# IMU_breakout.net
KiCad netlist of a schematic drawn in Altium Designer
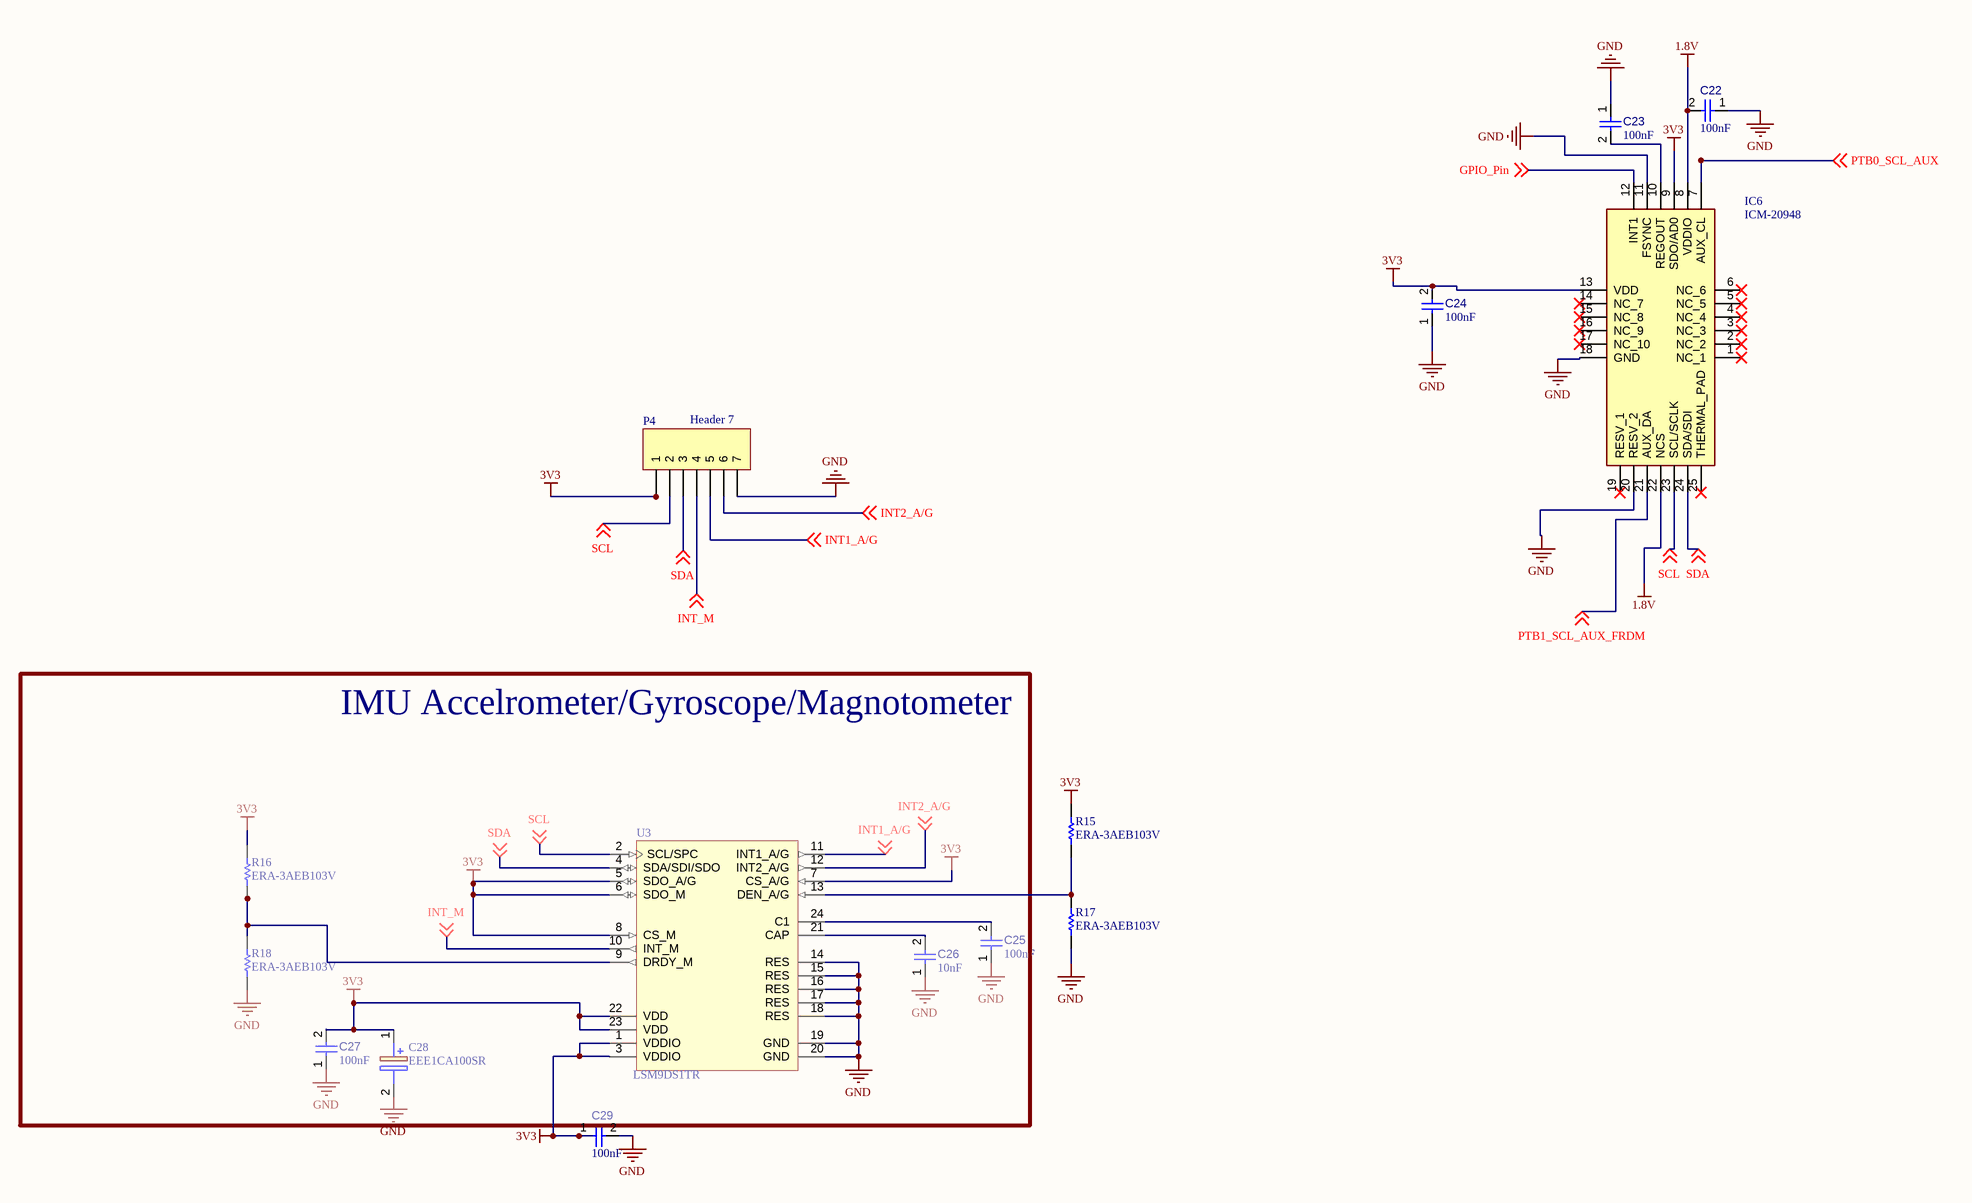
[diagram p0: IMU_breakout.SchDoc]

(export (version "E")
  (design (tool "Eeschema 10.0.6"))
  (components
    (comp (ref "C22")
      (value "100nF")
      (footprint "CAPC1608X90X40ML10T20")
      (description "Chip Capacitor, 100 nF, +/- 10%, 50 V, 0603 (1608 Metric)")
      (fields (field (name "TOLERANCE") "10%") (field (name "Comment") "Capacitor 100 nF +/-10% 50 V 0603"))
      (libsource (lib "James Cook University") (part "CAP-NP-2"))
    )
    (comp (ref "C23")
      (value "100nF")
      (footprint "CAPC1608X90X40ML10T20")
      (description "Chip Capacitor, 100 nF, +/- 10%, 50 V, 0603 (1608 Metric)")
      (fields (field (name "TOLERANCE") "10%") (field (name "Comment") "Capacitor 100 nF +/-10% 50 V 0603"))
      (libsource (lib "James Cook University") (part "CAP-NP-2"))
    )
    (comp (ref "C24")
      (value "100nF")
      (footprint "CAPC1608X90X40ML10T20")
      (description "Chip Capacitor, 100 nF, +/- 10%, 50 V, 0603 (1608 Metric)")
      (fields (field (name "TOLERANCE") "10%") (field (name "Comment") "Capacitor 100 nF +/-10% 50 V 0603"))
      (libsource (lib "James Cook University") (part "CAP-NP-2"))
    )
    (comp (ref "C25")
      (value "100nF")
      (footprint "CAPC1608X90X40ML10T20")
      (description "Chip Capacitor, 100 nF, +/- 10%, 50 V, 0603 (1608 Metric)")
      (fields (field (name "TOLERANCE") "10%") (field (name "Comment") "Capacitor 100 nF +/-10% 50 V 0603"))
      (libsource (lib "James Cook University") (part "CAP-NP-2"))
    )
    (comp (ref "C26")
      (value "10nF")
      (footprint "CAPC0402(1005)60_L")
      (description "Chip Capacitor, 10nF +/-20%, 50V, 0402, Thickness 0.6 mm")
      (fields (field (name "TOLERANCE") "5%") (field (name "Comment") "Capacitor 10nF +/-20% 50V 0402"))
      (libsource (lib "James Cook University") (part "CAP-NP-2"))
    )
    (comp (ref "C27")
      (value "100nF")
      (footprint "CAPC1608X90X40ML10T20")
      (description "Chip Capacitor, 100 nF, +/- 10%, 50 V, 0603 (1608 Metric)")
      (fields (field (name "TOLERANCE") "10%") (field (name "Comment") "Capacitor 100 nF +/-10% 50 V 0603"))
      (libsource (lib "James Cook University") (part "CAP-NP-2"))
    )
    (comp (ref "C28")
      (value "EEE1CA100SR")
      (footprint "SamacSys:CAPAE430X550N")
      (description "Capacitor Polarised")
      (libsource (lib "*") (part "EEE1CA100SR"))
    )
    (comp (ref "C29")
      (value "100nF")
      (footprint "CAPC1608X90X40ML10T20")
      (description "Chip Capacitor, 100 nF, +/- 10%, 50 V, 0603 (1608 Metric)")
      (fields (field (name "TOLERANCE") "10%") (field (name "Comment") "Capacitor 100 nF +/-10% 50 V 0603"))
      (libsource (lib "James Cook University") (part "CAP-NP-2"))
    )
    (comp (ref "IC6")
      (value "ICM-20948")
      (footprint "SamacSys:QFN40P300X300X105-25N-D")
      (description "Integrated Circuit")
      (fields (field (name "MOUSER PART NUMBER") "410-ICM-20948"))
      (libsource (lib "*") (part "ICM-20948"))
    )
    (comp (ref "P4")
      (value "Header 7")
      (footprint "HDR1X7")
      (description "Header, 7-Pin")
      (fields (field (name "PUBLISHER") "Altium Limited"))
      (libsource (lib "Miscellaneous Connectors") (part "Header 7"))
    )
    (comp (ref "R15")
      (value "ERA-3AEB103V")
      (footprint "RESC1608X55X30ML20T20")
      (fields (field (name "MANUFACTURER") "Panasonic"))
      (libsource (lib "Altium Content Vault") (part "RES"))
    )
    (comp (ref "R16")
      (value "ERA-3AEB103V")
      (footprint "RESC1608X55X30ML20T20")
      (fields (field (name "MANUFACTURER") "Panasonic"))
      (libsource (lib "Altium Content Vault") (part "RES"))
    )
    (comp (ref "R17")
      (value "ERA-3AEB103V")
      (footprint "RESC1608X55X30ML20T20")
      (fields (field (name "MANUFACTURER") "Panasonic"))
      (libsource (lib "Altium Content Vault") (part "RES"))
    )
    (comp (ref "R18")
      (value "ERA-3AEB103V")
      (footprint "RESC1608X55X30ML20T20")
      (fields (field (name "MANUFACTURER") "Panasonic"))
      (libsource (lib "Altium Content Vault") (part "RES"))
    )
    (comp (ref "U3")
      (value "LSM9DS1TR")
      (footprint "STM-LGA-24_3500X3000X1000")
      (fields (field (name "PARTNUMBER") "LSM9DS1") (field (name "MANUFACTURER") "STMicroelectronics"))
      (libsource (lib "Altium Content Vault") (part "STM-LSM9DS1-24"))
    )
  )
  (nets
    (net (code "1") (name "1.8V") (class "Default")
      (node (ref "C22") (pin "2") (pinfunction "2_2") (pintype "passive"))
      (node (ref "IC6") (pin "22") (pinfunction "NCS_22") (pintype "passive"))
      (node (ref "IC6") (pin "8") (pinfunction "VDDIO_8") (pintype "passive"))
    )
    (net (code "2") (name "3V3") (class "Default")
      (node (ref "C24") (pin "2") (pinfunction "2_2") (pintype "passive"))
      (node (ref "C27") (pin "2") (pinfunction "2_2") (pintype "passive"))
      (node (ref "C28") (pin "1") (pinfunction "+_1") (pintype "passive"))
      (node (ref "C29") (pin "1") (pinfunction "1_1") (pintype "passive"))
      (node (ref "IC6") (pin "13") (pinfunction "VDD_13") (pintype "passive"))
      (node (ref "IC6") (pin "9") (pinfunction "SDO/AD0_9") (pintype "passive"))
      (node (ref "P4") (pin "1") (pinfunction "1_1") (pintype "passive"))
      (node (ref "R15") (pin "2") (pinfunction "2_2") (pintype "passive"))
      (node (ref "R16") (pin "1") (pinfunction "1_1") (pintype "passive"))
      (node (ref "U3") (pin "1") (pinfunction "VDDIO_1") (pintype "power_in"))
      (node (ref "U3") (pin "22") (pinfunction "VDD_22") (pintype "power_in"))
      (node (ref "U3") (pin "23") (pinfunction "VDD_23") (pintype "power_in"))
      (node (ref "U3") (pin "3") (pinfunction "VDDIO_3") (pintype "power_in"))
      (node (ref "U3") (pin "5") (pinfunction "SDO_A/G_5") (pintype "bidirectional"))
      (node (ref "U3") (pin "6") (pinfunction "SDO_M_6") (pintype "bidirectional"))
      (node (ref "U3") (pin "7") (pinfunction "CS_A/G_7") (pintype "input"))
      (node (ref "U3") (pin "8") (pinfunction "CS_M_8") (pintype "input"))
    )
    (net (code "3") (name "GND") (class "Default")
      (node (ref "C22") (pin "1") (pinfunction "1_1") (pintype "passive"))
      (node (ref "C23") (pin "1") (pinfunction "1_1") (pintype "passive"))
      (node (ref "C24") (pin "1") (pinfunction "1_1") (pintype "passive"))
      (node (ref "C25") (pin "1") (pinfunction "1_1") (pintype "passive"))
      (node (ref "C26") (pin "1") (pinfunction "1_1") (pintype "passive"))
      (node (ref "C27") (pin "1") (pinfunction "1_1") (pintype "passive"))
      (node (ref "C29") (pin "2") (pinfunction "2_2") (pintype "passive"))
      (node (ref "IC6") (pin "11") (pinfunction "FSYNC_11") (pintype "passive"))
      (node (ref "IC6") (pin "18") (pinfunction "GND_18") (pintype "passive"))
      (node (ref "IC6") (pin "20") (pinfunction "RESV_2_20") (pintype "passive"))
      (node (ref "P4") (pin "7") (pinfunction "7_7") (pintype "passive"))
      (node (ref "R17") (pin "1") (pinfunction "1_1") (pintype "passive"))
      (node (ref "R18") (pin "2") (pinfunction "2_2") (pintype "passive"))
      (node (ref "U3") (pin "14") (pinfunction "RES_14") (pintype "passive"))
      (node (ref "U3") (pin "15") (pinfunction "RES_15") (pintype "passive"))
      (node (ref "U3") (pin "16") (pinfunction "RES_16") (pintype "passive"))
      (node (ref "U3") (pin "17") (pinfunction "RES_17") (pintype "passive"))
      (node (ref "U3") (pin "18") (pinfunction "RES_18") (pintype "passive"))
      (node (ref "U3") (pin "19") (pinfunction "GND_19") (pintype "power_in"))
      (node (ref "U3") (pin "20") (pinfunction "GND_20") (pintype "power_in"))
    )
    (net (code "4") (name "GPIO_Pin") (class "Default")
      (node (ref "IC6") (pin "12") (pinfunction "INT1_12") (pintype "passive"))
    )
    (net (code "5") (name "INT1_A{slash}G") (class "Default")
      (node (ref "P4") (pin "5") (pinfunction "5_5") (pintype "passive"))
      (node (ref "U3") (pin "11") (pinfunction "INT1_A/G_11") (pintype "output"))
    )
    (net (code "6") (name "INT2_A{slash}G") (class "Default")
      (node (ref "P4") (pin "6") (pinfunction "6_6") (pintype "passive"))
      (node (ref "U3") (pin "12") (pinfunction "INT2_A/G_12") (pintype "output"))
    )
    (net (code "7") (name "INT_M") (class "Default")
      (node (ref "P4") (pin "4") (pinfunction "4_4") (pintype "passive"))
      (node (ref "U3") (pin "10") (pinfunction "INT_M_10") (pintype "output"))
    )
    (net (code "8") (name "Net-(IC6-REGOUT)") (class "Default")
      (node (ref "C23") (pin "2") (pinfunction "2_2") (pintype "passive"))
      (node (ref "IC6") (pin "10") (pinfunction "REGOUT_10") (pintype "passive"))
    )
    (net (code "9") (name "Net-(U3-C1)") (class "Default")
      (node (ref "C25") (pin "2") (pinfunction "2_2") (pintype "passive"))
      (node (ref "U3") (pin "24") (pinfunction "C1_24") (pintype "passive"))
    )
    (net (code "10") (name "Net-(U3-CAP)") (class "Default")
      (node (ref "C26") (pin "2") (pinfunction "2_2") (pintype "passive"))
      (node (ref "U3") (pin "21") (pinfunction "CAP_21") (pintype "passive"))
    )
    (net (code "11") (name "Net-(U3-DEN_A{slash}G)") (class "Default")
      (node (ref "R15") (pin "1") (pinfunction "1_1") (pintype "passive"))
      (node (ref "R17") (pin "2") (pinfunction "2_2") (pintype "passive"))
      (node (ref "U3") (pin "13") (pinfunction "DEN_A/G_13") (pintype "input"))
    )
    (net (code "12") (name "Net-(U3-DRDY_M)") (class "Default")
      (node (ref "R16") (pin "2") (pinfunction "2_2") (pintype "passive"))
      (node (ref "R18") (pin "1") (pinfunction "1_1") (pintype "passive"))
      (node (ref "U3") (pin "9") (pinfunction "DRDY_M_9") (pintype "output"))
    )
    (net (code "13") (name "PTB0_SCL_AUX") (class "Default")
      (node (ref "IC6") (pin "7") (pinfunction "AUX_CL_7") (pintype "passive"))
    )
    (net (code "14") (name "PTB1_SCL_AUX_FRDM") (class "Default")
      (node (ref "IC6") (pin "21") (pinfunction "AUX_DA_21") (pintype "passive"))
    )
    (net (code "15") (name "SCL") (class "Default")
      (node (ref "IC6") (pin "23") (pinfunction "SCL/SCLK_23") (pintype "passive"))
      (node (ref "P4") (pin "2") (pinfunction "2_2") (pintype "passive"))
      (node (ref "U3") (pin "2") (pinfunction "SCL/SPC_2") (pintype "input"))
    )
    (net (code "16") (name "SDA") (class "Default")
      (node (ref "IC6") (pin "24") (pinfunction "SDA/SDI_24") (pintype "passive"))
      (node (ref "P4") (pin "3") (pinfunction "3_3") (pintype "passive"))
      (node (ref "U3") (pin "4") (pinfunction "SDA/SDI/SDO_4") (pintype "bidirectional"))
    )
    (net (code "17") (name "unconnected-(C28---Pad2)") (class "Default")
      (node (ref "C28") (pin "2") (pinfunction "-_2") (pintype "passive"))
    )
    (net (code "18") (name "unconnected-(IC6-NC_1-Pad1)") (class "Default")
      (node (ref "IC6") (pin "1") (pinfunction "NC_1_1") (pintype "passive+no_connect"))
    )
    (net (code "19") (name "unconnected-(IC6-NC_2-Pad2)") (class "Default")
      (node (ref "IC6") (pin "2") (pinfunction "NC_2_2") (pintype "passive+no_connect"))
    )
    (net (code "20") (name "unconnected-(IC6-NC_3-Pad3)") (class "Default")
      (node (ref "IC6") (pin "3") (pinfunction "NC_3_3") (pintype "passive+no_connect"))
    )
    (net (code "21") (name "unconnected-(IC6-NC_4-Pad4)") (class "Default")
      (node (ref "IC6") (pin "4") (pinfunction "NC_4_4") (pintype "passive+no_connect"))
    )
    (net (code "22") (name "unconnected-(IC6-NC_5-Pad5)") (class "Default")
      (node (ref "IC6") (pin "5") (pinfunction "NC_5_5") (pintype "passive+no_connect"))
    )
    (net (code "23") (name "unconnected-(IC6-NC_6-Pad6)") (class "Default")
      (node (ref "IC6") (pin "6") (pinfunction "NC_6_6") (pintype "passive+no_connect"))
    )
    (net (code "24") (name "unconnected-(IC6-NC_7-Pad14)") (class "Default")
      (node (ref "IC6") (pin "14") (pinfunction "NC_7_14") (pintype "passive+no_connect"))
    )
    (net (code "25") (name "unconnected-(IC6-NC_8-Pad15)") (class "Default")
      (node (ref "IC6") (pin "15") (pinfunction "NC_8_15") (pintype "passive+no_connect"))
    )
    (net (code "26") (name "unconnected-(IC6-NC_9-Pad16)") (class "Default")
      (node (ref "IC6") (pin "16") (pinfunction "NC_9_16") (pintype "passive+no_connect"))
    )
    (net (code "27") (name "unconnected-(IC6-NC_10-Pad17)") (class "Default")
      (node (ref "IC6") (pin "17") (pinfunction "NC_10_17") (pintype "passive+no_connect"))
    )
    (net (code "28") (name "unconnected-(IC6-RESV_1-Pad19)") (class "Default")
      (node (ref "IC6") (pin "19") (pinfunction "RESV_1_19") (pintype "passive+no_connect"))
    )
    (net (code "29") (name "unconnected-(IC6-THERMAL_PAD-Pad25)") (class "Default")
      (node (ref "IC6") (pin "25") (pinfunction "THERMAL_PAD_25") (pintype "passive+no_connect"))
    )
  )
)
